# LED_board.net
KiCad netlist of a schematic drawn in EAGLE
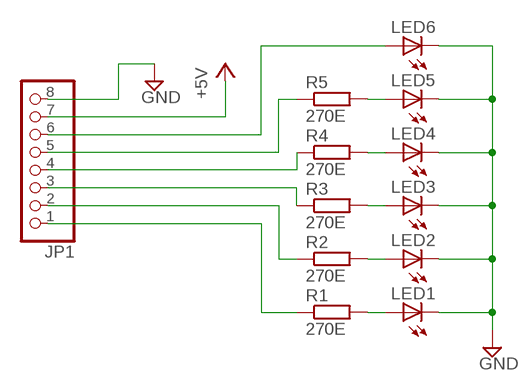
[diagram p0: schematic, sheet 1]

(export (version "E")
  (design (tool "Eeschema 10.0.6"))
  (components
    (comp (ref "JP1")
      (value "PINHD-1X8")
      (footprint "eagle-import:1X08")
      (libsource (lib "eagle-import") (part "PINHD-1X8"))
    )
    (comp (ref "LED1")
      (value "LED5MM")
      (footprint "eagle-import:LED5MM")
      (libsource (lib "eagle-import") (part "LED5MM"))
    )
    (comp (ref "LED2")
      (value "LED5MM")
      (footprint "eagle-import:LED5MM")
      (libsource (lib "eagle-import") (part "LED5MM"))
    )
    (comp (ref "LED3")
      (value "LED5MM")
      (footprint "eagle-import:LED5MM")
      (libsource (lib "eagle-import") (part "LED5MM"))
    )
    (comp (ref "LED4")
      (value "LED5MM")
      (footprint "eagle-import:LED5MM")
      (libsource (lib "eagle-import") (part "LED5MM"))
    )
    (comp (ref "LED5")
      (value "LED5MM")
      (footprint "eagle-import:LED5MM")
      (libsource (lib "eagle-import") (part "LED5MM"))
    )
    (comp (ref "LED6")
      (value "LED5MM")
      (footprint "eagle-import:LED5MM")
      (libsource (lib "eagle-import") (part "LED5MM"))
    )
    (comp (ref "R1")
      (value "270E")
      (footprint "eagle-import:R1206")
      (libsource (lib "eagle-import") (part "R-EU_R1206"))
    )
    (comp (ref "R2")
      (value "270E")
      (footprint "eagle-import:R1206")
      (libsource (lib "eagle-import") (part "R-EU_R1206"))
    )
    (comp (ref "R3")
      (value "270E")
      (footprint "eagle-import:R1206")
      (libsource (lib "eagle-import") (part "R-EU_R1206"))
    )
    (comp (ref "R4")
      (value "270E")
      (footprint "eagle-import:R1206")
      (libsource (lib "eagle-import") (part "R-EU_R1206"))
    )
    (comp (ref "R5")
      (value "270E")
      (footprint "eagle-import:R1206")
      (libsource (lib "eagle-import") (part "R-EU_R1206"))
    )
  )
  (nets
    (net (code "1") (name "+5V") (class "Default")
      (node (ref "JP1") (pin "7") (pinfunction "7_7") (pintype "passive"))
    )
    (net (code "2") (name "GND") (class "Default")
      (node (ref "JP1") (pin "8") (pinfunction "8_8") (pintype "passive"))
      (node (ref "LED1") (pin "K") (pinfunction "C_K") (pintype "passive"))
      (node (ref "LED2") (pin "K") (pinfunction "C_K") (pintype "passive"))
      (node (ref "LED3") (pin "K") (pinfunction "C_K") (pintype "passive"))
      (node (ref "LED4") (pin "K") (pinfunction "C_K") (pintype "passive"))
      (node (ref "LED5") (pin "K") (pinfunction "C_K") (pintype "passive"))
      (node (ref "LED6") (pin "K") (pinfunction "C_K") (pintype "passive"))
    )
    (net (code "3") (name "Net-(JP1-Pad1)") (class "Default")
      (node (ref "JP1") (pin "1") (pinfunction "1_1") (pintype "passive"))
      (node (ref "R1") (pin "1") (pinfunction "1_1") (pintype "passive"))
    )
    (net (code "4") (name "Net-(JP1-Pad2)") (class "Default")
      (node (ref "JP1") (pin "2") (pinfunction "2_2") (pintype "passive"))
      (node (ref "R2") (pin "1") (pinfunction "1_1") (pintype "passive"))
    )
    (net (code "5") (name "Net-(JP1-Pad3)") (class "Default")
      (node (ref "JP1") (pin "3") (pinfunction "3_3") (pintype "passive"))
      (node (ref "R3") (pin "1") (pinfunction "1_1") (pintype "passive"))
    )
    (net (code "6") (name "Net-(JP1-Pad4)") (class "Default")
      (node (ref "JP1") (pin "4") (pinfunction "4_4") (pintype "passive"))
      (node (ref "R4") (pin "1") (pinfunction "1_1") (pintype "passive"))
    )
    (net (code "7") (name "Net-(JP1-Pad5)") (class "Default")
      (node (ref "JP1") (pin "5") (pinfunction "5_5") (pintype "passive"))
      (node (ref "R5") (pin "1") (pinfunction "1_1") (pintype "passive"))
    )
    (net (code "8") (name "Net-(JP1-Pad6)") (class "Default")
      (node (ref "JP1") (pin "6") (pinfunction "6_6") (pintype "passive"))
      (node (ref "LED6") (pin "A") (pinfunction "A_A") (pintype "passive"))
    )
    (net (code "9") (name "Net-(LED1-PadA)") (class "Default")
      (node (ref "LED1") (pin "A") (pinfunction "A_A") (pintype "passive"))
      (node (ref "R1") (pin "2") (pinfunction "2_2") (pintype "passive"))
    )
    (net (code "10") (name "Net-(LED2-PadA)") (class "Default")
      (node (ref "LED2") (pin "A") (pinfunction "A_A") (pintype "passive"))
      (node (ref "R2") (pin "2") (pinfunction "2_2") (pintype "passive"))
    )
    (net (code "11") (name "Net-(LED3-PadA)") (class "Default")
      (node (ref "LED3") (pin "A") (pinfunction "A_A") (pintype "passive"))
      (node (ref "R3") (pin "2") (pinfunction "2_2") (pintype "passive"))
    )
    (net (code "12") (name "Net-(LED4-PadA)") (class "Default")
      (node (ref "LED4") (pin "A") (pinfunction "A_A") (pintype "passive"))
      (node (ref "R4") (pin "2") (pinfunction "2_2") (pintype "passive"))
    )
    (net (code "13") (name "Net-(LED5-PadA)") (class "Default")
      (node (ref "LED5") (pin "A") (pinfunction "A_A") (pintype "passive"))
      (node (ref "R5") (pin "2") (pinfunction "2_2") (pintype "passive"))
    )
  )
)
